# sensorboardschematic.net
KiCad netlist of a schematic drawn in EasyEDA Pro
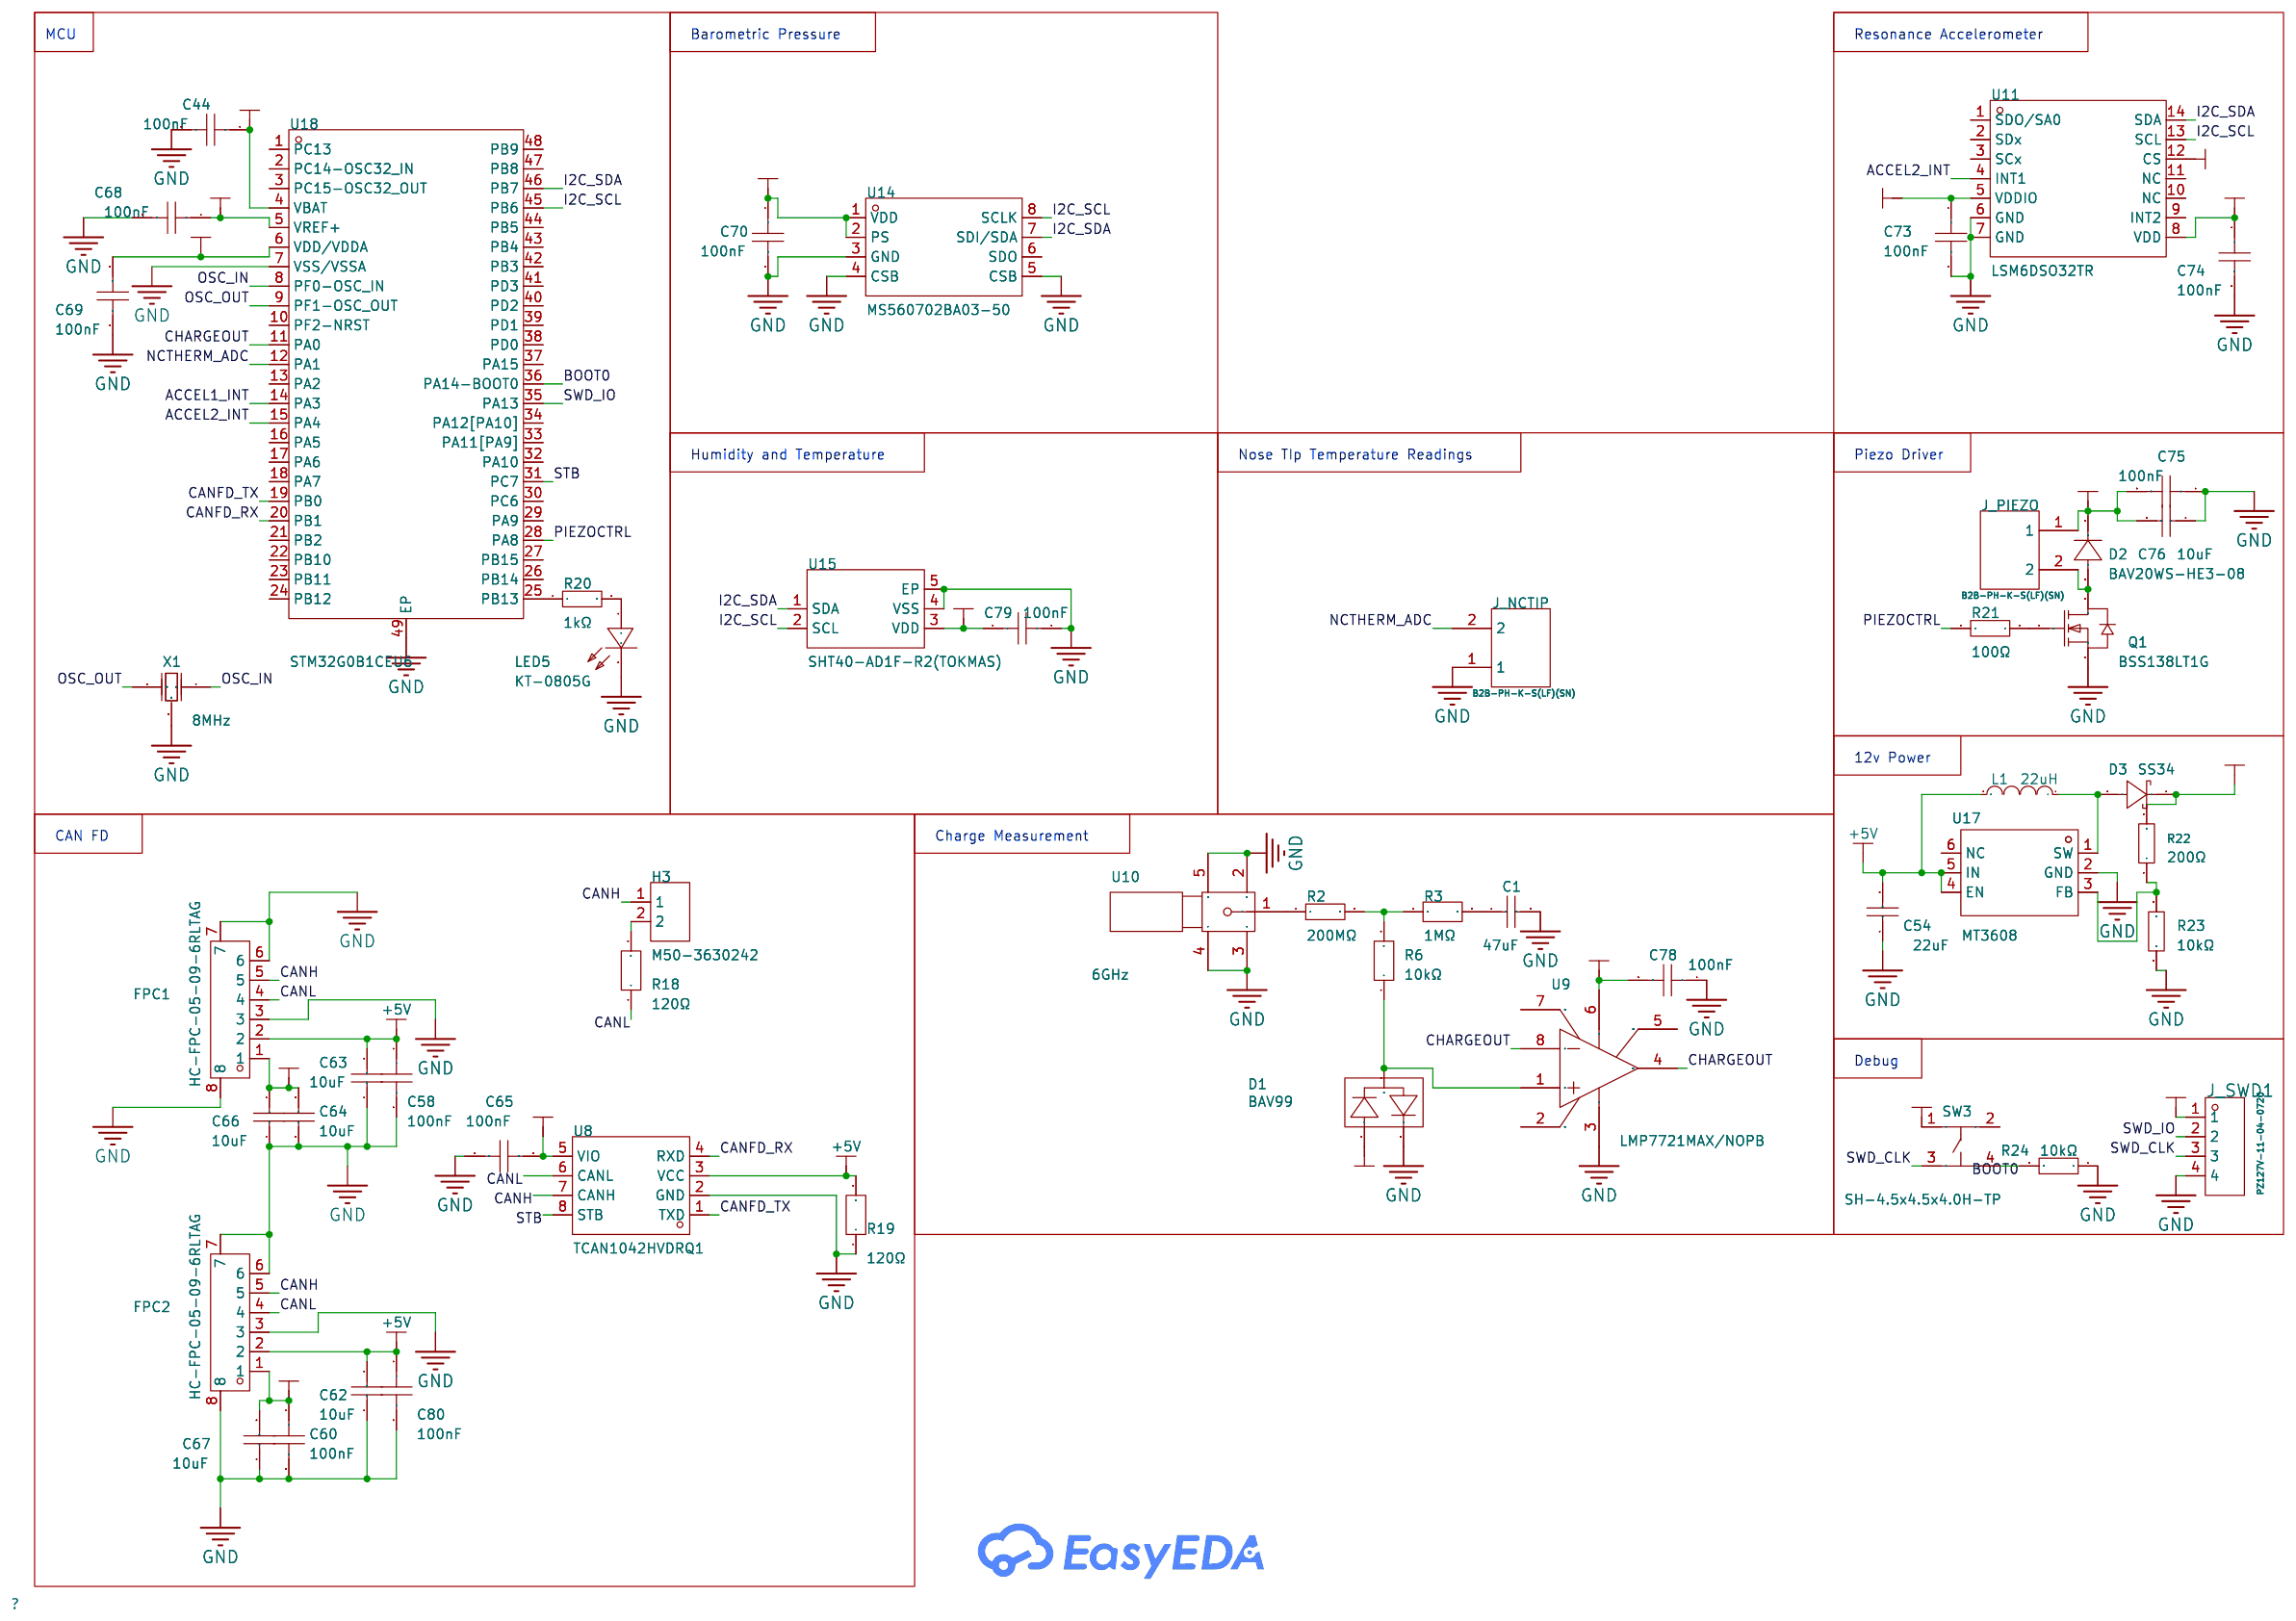
[diagram p0: schematic sheet]

(export (version "E")
  (design (tool "Eeschema 10.0.6"))
  (components
    (comp (ref "C1")
      (value "47uF")
      (footprint "easyedapro:C0805")
      (description "Capacitance:47uF Tolerance:±20% Tolerance:±20% Voltage Rating:6.3V Temperature Coefficient:X5R")
      (fields
        (field (name "Manufacturer Part") "CL21A476MQYNNNE")
        (field (name "Manufacturer") "SAMSUNG(三星)")
      )
      (libsource (lib "easyedapro") (part "CL21A476MQYNNNE"))
    )
    (comp (ref "C44")
      (value "100nF")
      (footprint "easyedapro:C0402")
      (description "Capacitance:100nF Tolerance:±10% Tolerance:±10% Voltage Rating:16V Temperature Coefficient:X7R")
      (fields
        (field (name "Manufacturer Part") "CL05B104KO5NNNC")
        (field (name "Manufacturer") "SAMSUNG(三星)")
      )
      (libsource (lib "easyedapro") (part "CL05B104KO5NNNC"))
    )
    (comp (ref "C54")
      (value "22uF")
      (footprint "easyedapro:C1206")
      (description "Capacitance:22uF Tolerance:±10% Tolerance:±10% Voltage Rating:25V Temperature Coefficient:X5R")
      (fields
        (field (name "Manufacturer Part") "CL31A226KAHNNNE")
        (field (name "Manufacturer") "SAMSUNG(三星)")
      )
      (libsource (lib "easyedapro") (part "CL31A226KAHNNNE"))
    )
    (comp (ref "C58")
      (value "100nF")
      (footprint "easyedapro:C0402")
      (description "Capacitance:100nF Tolerance:±10% Tolerance:±10% Voltage Rating:16V Temperature Coefficient:X7R")
      (fields
        (field (name "Manufacturer Part") "CL05B104KO5NNNC")
        (field (name "Manufacturer") "SAMSUNG(三星)")
      )
      (libsource (lib "easyedapro") (part "CL05B104KO5NNNC"))
    )
    (comp (ref "C60")
      (value "100nF")
      (footprint "easyedapro:C0402")
      (description "Capacitance:100nF Tolerance:±10% Tolerance:±10% Voltage Rating:16V Temperature Coefficient:X7R")
      (fields
        (field (name "Manufacturer Part") "CL05B104KO5NNNC")
        (field (name "Manufacturer") "SAMSUNG(三星)")
      )
      (libsource (lib "easyedapro") (part "CL05B104KO5NNNC"))
    )
    (comp (ref "C62")
      (value "10uF")
      (footprint "easyedapro:C0402")
      (description "Capacitance:10uF Tolerance:±20% Tolerance:±20% Voltage Rating:6.3V Temperature Coefficient:X5R")
      (fields
        (field (name "Manufacturer Part") "CL05A106MQ5NUNC")
        (field (name "Manufacturer") "SAMSUNG(三星)")
      )
      (libsource (lib "easyedapro") (part "CL05A106MQ5NUNC"))
    )
    (comp (ref "C63")
      (value "10uF")
      (footprint "easyedapro:C0402")
      (description "Capacitance:10uF Tolerance:±20% Tolerance:±20% Voltage Rating:6.3V Temperature Coefficient:X5R")
      (fields
        (field (name "Manufacturer Part") "CL05A106MQ5NUNC")
        (field (name "Manufacturer") "SAMSUNG(三星)")
      )
      (libsource (lib "easyedapro") (part "CL05A106MQ5NUNC"))
    )
    (comp (ref "C64")
      (value "10uF")
      (footprint "easyedapro:C0402")
      (description "Capacitance:10uF Tolerance:±20% Tolerance:±20% Voltage Rating:6.3V Temperature Coefficient:X5R")
      (fields
        (field (name "Manufacturer Part") "CL05A106MQ5NUNC")
        (field (name "Manufacturer") "SAMSUNG(三星)")
      )
      (libsource (lib "easyedapro") (part "CL05A106MQ5NUNC"))
    )
    (comp (ref "C65")
      (value "100nF")
      (footprint "easyedapro:C0402")
      (description "Capacitance:100nF Tolerance:±10% Tolerance:±10% Voltage Rating:16V Temperature Coefficient:X7R")
      (fields
        (field (name "Manufacturer Part") "CL05B104KO5NNNC")
        (field (name "Manufacturer") "SAMSUNG(三星)")
      )
      (libsource (lib "easyedapro") (part "CL05B104KO5NNNC"))
    )
    (comp (ref "C66")
      (value "10uF")
      (footprint "easyedapro:C0402")
      (description "Capacitance:10uF Tolerance:±20% Tolerance:±20% Voltage Rating:6.3V Temperature Coefficient:X5R")
      (fields
        (field (name "Manufacturer Part") "CL05A106MQ5NUNC")
        (field (name "Manufacturer") "SAMSUNG(三星)")
      )
      (libsource (lib "easyedapro") (part "CL05A106MQ5NUNC"))
    )
    (comp (ref "C67")
      (value "10uF")
      (footprint "easyedapro:C0402")
      (description "Capacitance:10uF Tolerance:±20% Tolerance:±20% Voltage Rating:6.3V Temperature Coefficient:X5R")
      (fields
        (field (name "Manufacturer Part") "CL05A106MQ5NUNC")
        (field (name "Manufacturer") "SAMSUNG(三星)")
      )
      (libsource (lib "easyedapro") (part "CL05A106MQ5NUNC"))
    )
    (comp (ref "C68")
      (value "100nF")
      (footprint "easyedapro:C0402")
      (description "Capacitance:100nF Tolerance:±10% Tolerance:±10% Voltage Rating:16V Temperature Coefficient:X7R")
      (fields
        (field (name "Manufacturer Part") "CL05B104KO5NNNC")
        (field (name "Manufacturer") "SAMSUNG(三星)")
      )
      (libsource (lib "easyedapro") (part "CL05B104KO5NNNC"))
    )
    (comp (ref "C69")
      (value "100nF")
      (footprint "easyedapro:C0402")
      (description "Capacitance:100nF Tolerance:±10% Tolerance:±10% Voltage Rating:16V Temperature Coefficient:X7R")
      (fields
        (field (name "Manufacturer Part") "CL05B104KO5NNNC")
        (field (name "Manufacturer") "SAMSUNG(三星)")
      )
      (libsource (lib "easyedapro") (part "CL05B104KO5NNNC"))
    )
    (comp (ref "C70")
      (value "100nF")
      (footprint "easyedapro:C0402")
      (description "Capacitance:100nF Tolerance:±10% Tolerance:±10% Voltage Rating:16V Temperature Coefficient:X7R")
      (fields
        (field (name "Manufacturer Part") "CL05B104KO5NNNC")
        (field (name "Manufacturer") "SAMSUNG(三星)")
      )
      (libsource (lib "easyedapro") (part "CL05B104KO5NNNC"))
    )
    (comp (ref "C73")
      (value "100nF")
      (footprint "easyedapro:C0402")
      (description "Capacitance:100nF Tolerance:±10% Tolerance:±10% Voltage Rating:16V Temperature Coefficient:X7R")
      (fields
        (field (name "Manufacturer Part") "CL05B104KO5NNNC")
        (field (name "Manufacturer") "SAMSUNG(三星)")
      )
      (libsource (lib "easyedapro") (part "CL05B104KO5NNNC"))
    )
    (comp (ref "C74")
      (value "100nF")
      (footprint "easyedapro:C0402")
      (description "Capacitance:100nF Tolerance:±10% Tolerance:±10% Voltage Rating:16V Temperature Coefficient:X7R")
      (fields
        (field (name "Manufacturer Part") "CL05B104KO5NNNC")
        (field (name "Manufacturer") "SAMSUNG(三星)")
      )
      (libsource (lib "easyedapro") (part "CL05B104KO5NNNC"))
    )
    (comp (ref "C75")
      (value "100nF")
      (footprint "easyedapro:C0402")
      (description "Capacitance:100nF Tolerance:±10% Tolerance:±10% Voltage Rating:16V Temperature Coefficient:X7R")
      (fields
        (field (name "Manufacturer Part") "CL05B104KO5NNNC")
        (field (name "Manufacturer") "SAMSUNG(三星)")
      )
      (libsource (lib "easyedapro") (part "CL05B104KO5NNNC"))
    )
    (comp (ref "C76")
      (value "10uF")
      (footprint "easyedapro:C0402")
      (description "Capacitance:10uF Tolerance:±20% Tolerance:±20% Voltage Rating:6.3V Temperature Coefficient:X5R")
      (fields
        (field (name "Manufacturer Part") "CL05A106MQ5NUNC")
        (field (name "Manufacturer") "SAMSUNG(三星)")
      )
      (libsource (lib "easyedapro") (part "CL05A106MQ5NUNC"))
    )
    (comp (ref "C78")
      (value "100nF")
      (footprint "easyedapro:C0402")
      (description "Capacitance:100nF Tolerance:±10% Tolerance:±10% Voltage Rating:16V Temperature Coefficient:X7R")
      (fields
        (field (name "Manufacturer Part") "CL05B104KO5NNNC")
        (field (name "Manufacturer") "SAMSUNG(三星)")
      )
      (libsource (lib "easyedapro") (part "CL05B104KO5NNNC"))
    )
    (comp (ref "C79")
      (value "100nF")
      (footprint "easyedapro:C0402")
      (description "Capacitance:100nF Tolerance:±10% Tolerance:±10% Voltage Rating:16V Temperature Coefficient:X7R")
      (fields
        (field (name "Manufacturer Part") "CL05B104KO5NNNC")
        (field (name "Manufacturer") "SAMSUNG(三星)")
      )
      (libsource (lib "easyedapro") (part "CL05B104KO5NNNC"))
    )
    (comp (ref "C80")
      (value "100nF")
      (footprint "easyedapro:C0402")
      (description "Capacitance:100nF Tolerance:±10% Tolerance:±10% Voltage Rating:16V Temperature Coefficient:X7R")
      (fields
        (field (name "Manufacturer Part") "CL05B104KO5NNNC")
        (field (name "Manufacturer") "SAMSUNG(三星)")
      )
      (libsource (lib "easyedapro") (part "CL05B104KO5NNNC"))
    )
    (comp (ref "D1")
      (value "BAV99")
      (footprint "easyedapro:SOT-23-3_L2.9-W1.3-P1.90-LS2.4-BR")
      (fields (field (name "Manufacturer") "JSMSEMI(杰盛微)"))
      (libsource (lib "easyedapro") (part "BAV99_C916421"))
    )
    (comp (ref "D2")
      (value "BAV20WS-HE3-08")
      (footprint "easyedapro:SOD-323_L1.8-W1.3-LS2.7-RD")
      (fields (field (name "Manufacturer") "VISHAY(威世)"))
      (libsource (lib "easyedapro") (part "BAV20WS-HE3-08"))
    )
    (comp (ref "D3")
      (value "SS34")
      (footprint "easyedapro:SMA_L4.2-W2.7-LS5.0-RD")
      (fields (field (name "Manufacturer") "JSMSEMI(杰盛微)"))
      (libsource (lib "easyedapro") (part "SS34_C2837271"))
    )
    (comp (ref "FPC1")
      (value "HC-FPC-05-09-6RLTAG")
      (footprint "easyedapro:FPC-SMD_6P-P0.50_HC-FPC-05-09-6RLTAG")
      (fields (field (name "Manufacturer") "HCTL(华灿天禄)"))
      (libsource (lib "easyedapro") (part "HC-FPC-05-09-6RLTAG"))
    )
    (comp (ref "FPC2")
      (value "HC-FPC-05-09-6RLTAG")
      (footprint "easyedapro:FPC-SMD_6P-P0.50_HC-FPC-05-09-6RLTAG")
      (fields (field (name "Manufacturer") "HCTL(华灿天禄)"))
      (libsource (lib "easyedapro") (part "HC-FPC-05-09-6RLTAG"))
    )
    (comp (ref "H3")
      (value "M50-3630242")
      (footprint "easyedapro:HDR-SMD_2P-P1.27_M50-3630242")
      (fields (field (name "Manufacturer") "Harwin"))
      (libsource (lib "easyedapro") (part "M50-3630242"))
    )
    (comp (ref "J_NCTIP")
      (value "B2B-PH-K-S(LF)(SN)")
      (footprint "easyedapro:CONN-TH_B2B-PH-K-S")
      (fields (field (name "Manufacturer") "JST"))
      (libsource (lib "easyedapro") (part "B2B-PH-K-S(LF)(SN)"))
    )
    (comp (ref "J_PIEZO")
      (value "B2B-PH-K-S(LF)(SN)")
      (footprint "easyedapro:CONN-TH_B2B-PH-K-S")
      (fields (field (name "Manufacturer") "JST"))
      (libsource (lib "easyedapro") (part "B2B-PH-K-S(LF)(SN)"))
    )
    (comp (ref "J_SWD1")
      (value "PZ127V-11-04-0720")
      (footprint "easyedapro:HDR-TH_4P-P1.27-V-M")
      (fields (field (name "Manufacturer") "XFCN(兴飞)"))
      (libsource (lib "easyedapro") (part "PZ127V-11-04-0720"))
    )
    (comp (ref "L1")
      (value "22uH")
      (footprint "easyedapro:IND-SMD_L3.2-W2.5")
      (fields (field (name "Manufacturer Part") "NLV32T-220J-EF") (field (name "Manufacturer") "TDK"))
      (libsource (lib "easyedapro") (part "NLV32T-220J-EF"))
    )
    (comp (ref "LED5")
      (value "KT-0805G")
      (footprint "easyedapro:LED0805-R-RD")
      (fields (field (name "Manufacturer") "KENTO"))
      (libsource (lib "easyedapro") (part "0805G (Green)"))
    )
    (comp (ref "Q1")
      (value "BSS138LT1G")
      (footprint "easyedapro:SOT-23-3_L2.9-W1.6-P1.90-LS2.8-BR")
      (fields (field (name "Manufacturer") "onsemi(安森美)"))
      (libsource (lib "easyedapro") (part "BSS138LT1G"))
    )
    (comp (ref "R2")
      (value "200MΩ")
      (footprint "easyedapro:RES-TH_L14.7-W2.54-P10.2-D0.8")
      (fields (field (name "Manufacturer Part") "SM102032006FE") (field (name "Manufacturer") "Ohmite"))
      (libsource (lib "easyedapro") (part "SM102032006FE"))
    )
    (comp (ref "R3")
      (value "1MΩ")
      (footprint "easyedapro:R0402")
      (fields (field (name "Manufacturer Part") "FRC0402F1004TS") (field (name "Manufacturer") "FOJAN(富捷)"))
      (libsource (lib "easyedapro") (part "FRC0402F1004TS"))
    )
    (comp (ref "R6")
      (value "10kΩ")
      (footprint "easyedapro:R0402")
      (fields (field (name "Manufacturer Part") "FRC0402F1002TS") (field (name "Manufacturer") "FOJAN(富捷)"))
      (libsource (lib "easyedapro") (part "FRC0402F1002TS"))
    )
    (comp (ref "R18")
      (value "120Ω")
      (footprint "easyedapro:R0402")
      (fields (field (name "Manufacturer Part") "FRC0402F1200TS") (field (name "Manufacturer") "FOJAN(富捷)"))
      (libsource (lib "easyedapro") (part "FRC0402F1200TS"))
    )
    (comp (ref "R19")
      (value "120Ω")
      (footprint "easyedapro:R0402")
      (fields (field (name "Manufacturer Part") "FRC0402F1200TS") (field (name "Manufacturer") "FOJAN(富捷)"))
      (libsource (lib "easyedapro") (part "FRC0402F1200TS"))
    )
    (comp (ref "R20")
      (value "1kΩ")
      (footprint "easyedapro:R0402")
      (fields
        (field (name "Manufacturer Part") "0402WGF1001TCE")
        (field (name "Manufacturer") "UNI-ROYAL(厚声)")
      )
      (libsource (lib "easyedapro") (part "0402WGF1001TCE"))
    )
    (comp (ref "R21")
      (value "100Ω")
      (footprint "easyedapro:R0402")
      (fields
        (field (name "Manufacturer Part") "0402WGF1000TCE")
        (field (name "Manufacturer") "UNI-ROYAL(厚声)")
      )
      (libsource (lib "easyedapro") (part "0402WGF1000TCE"))
    )
    (comp (ref "R22")
      (value "200Ω")
      (footprint "easyedapro:R0603")
      (fields
        (field (name "Manufacturer Part") "0603WAF2000T5E")
        (field (name "Manufacturer") "UNI-ROYAL(厚声)")
      )
      (libsource (lib "easyedapro") (part "0603WAF2000T5E"))
    )
    (comp (ref "R23")
      (value "10kΩ")
      (footprint "easyedapro:R0402")
      (fields
        (field (name "Manufacturer Part") "0402WGF1002TCE")
        (field (name "Manufacturer") "UNI-ROYAL(厚声)")
      )
      (libsource (lib "easyedapro") (part "0402WGF1002TCE"))
    )
    (comp (ref "R24")
      (value "10kΩ")
      (footprint "easyedapro:R0402")
      (fields
        (field (name "Manufacturer Part") "0402WGF1002TCE")
        (field (name "Manufacturer") "UNI-ROYAL(厚声)")
      )
      (libsource (lib "easyedapro") (part "0402WGF1002TCE"))
    )
    (comp (ref "SW3")
      (value "SH-4.5x4.5x4.0H-TP")
      (footprint "easyedapro:SW-SMD_4P-SH-4.5X4.5X4.0H-TP")
      (fields (field (name "Manufacturer") "SHOU HAN(首韩)"))
      (libsource (lib "easyedapro") (part "SH-4.5X4.5X4.0H-TP"))
    )
    (comp (ref "U8")
      (value "TCAN1042HVDRQ1")
      (footprint "easyedapro:SOIC-8_L4.9-W3.9-P1.27-LS6.0-BL")
      (fields (field (name "Manufacturer") "TI(德州仪器)"))
      (libsource (lib "easyedapro") (part "TCAN1042HVDRQ1"))
    )
    (comp (ref "U9")
      (value "LMP7721MAX/NOPB")
      (footprint "easyedapro:SOIC-8_L4.9-W3.9-P1.27-LS6.0-BL")
      (fields (field (name "Manufacturer") "TI(德州仪器)"))
      (libsource (lib "easyedapro") (part "LMP7721MAX/NOPB"))
    )
    (comp (ref "U10")
      (value "6GHz")
      (footprint "easyedapro:MMCX-TH_DL-MMCX-KWE")
      (fields
        (field (name "Manufacturer Part") "BWMMCX-KWE")
        (field (name "Manufacturer") "BAT WIRELESS(蝙蝠无线)")
      )
      (libsource (lib "easyedapro") (part "BWMMCX-KWE"))
    )
    (comp (ref "U11")
      (value "LSM6DSO32TR")
      (footprint "easyedapro:LGA-14_L3.0-W2.5-P0.50-TL")
      (description "Sensor Type:加速度计陀螺仪 Operating Temperature:-40°C~+85°C Operating Temperature:-40°C~+85°C")
      (fields (field (name "Manufacturer") "ST(意法半导体)"))
      (libsource (lib "easyedapro") (part "LSM6DSO32TR"))
    )
    (comp (ref "U14")
      (value "MS560702BA03-50")
      (footprint "easyedapro:SENSOR-SMD_MS560702BA03-50")
      (fields (field (name "Manufacturer") "TE Connectivity(泰科电子)"))
      (libsource (lib "easyedapro") (part "MS560702BA03-50"))
    )
    (comp (ref "U15")
      (value "SHT40-AD1F-R2(TOKMAS)")
      (footprint "easyedapro:DFN-4_L1.5-W1.5-P0.80-TL-EP")
      (fields (field (name "Manufacturer") "Tokmas(托克马斯)"))
      (libsource (lib "easyedapro") (part "SHT40-AD1F-R2(TOKMAS)"))
    )
    (comp (ref "U17")
      (value "MT3608")
      (footprint "easyedapro:SOT-23-6_L2.9-W1.6-P0.95-LS2.8-BL")
      (fields (field (name "Manufacturer") "西安航天民芯"))
      (libsource (lib "easyedapro") (part "MT3608"))
    )
    (comp (ref "U18")
      (value "STM32G0B1CEU6")
      (footprint "easyedapro:UFQFPN-48_L7.0-W7.0-P0.50-BL-EP")
      (fields (field (name "Manufacturer") "ST(意法半导体)"))
      (libsource (lib "easyedapro") (part "STM32G0B1CEU6"))
    )
    (comp (ref "X1")
      (value "8MHz")
      (footprint "easyedapro:OSC-SMD_3P-L3.2-W1.3-P1.20-L")
      (fields
        (field (name "Manufacturer Part") "CSTNE8M00GH5C000R0")
        (field (name "Manufacturer") "muRata(村田)")
      )
      (libsource (lib "easyedapro") (part "CSTNE8M00GH5C000R0"))
    )
  )
  (nets
    (net (code "1") (name "+5V") (class "Default")
      (node (ref "C54") (pin "2") (pinfunction "2_2") (pintype "input"))
      (node (ref "C58") (pin "1") (pinfunction "1_1") (pintype "unspecified"))
      (node (ref "C62") (pin "2") (pinfunction "2_2") (pintype "input"))
      (node (ref "C63") (pin "2") (pinfunction "2_2") (pintype "input"))
      (node (ref "C80") (pin "1") (pinfunction "1_1") (pintype "unspecified"))
      (node (ref "FPC1") (pin "2") (pinfunction "2_2") (pintype "unspecified"))
      (node (ref "FPC2") (pin "2") (pinfunction "2_2") (pintype "unspecified"))
      (node (ref "L1") (pin "2") (pinfunction "2_2") (pintype "unspecified"))
      (node (ref "R19") (pin "2") (pinfunction "2_2") (pintype "unspecified"))
      (node (ref "U17") (pin "4") (pinfunction "EN_4") (pintype "unspecified"))
      (node (ref "U17") (pin "5") (pinfunction "IN_5") (pintype "unspecified"))
      (node (ref "U8") (pin "3") (pinfunction "VCC_3") (pintype "unspecified"))
    )
    (net (code "2") (name "+12V") (class "Default")
      (node (ref "C75") (pin "2") (pinfunction "2_2") (pintype "unspecified"))
      (node (ref "C76") (pin "2") (pinfunction "2_2") (pintype "input"))
      (node (ref "D2") (pin "1") (pinfunction "C_1") (pintype "unspecified"))
      (node (ref "D3") (pin "1") (pinfunction "K_1") (pintype "unspecified"))
      (node (ref "J_PIEZO") (pin "1") (pinfunction "1_1") (pintype "input"))
      (node (ref "R22") (pin "2") (pinfunction "2_2") (pintype "input"))
    )
    (net (code "3") (name "/ACCEL1_INT") (class "Default")
      (node (ref "U18") (pin "14") (pinfunction "PA3_14") (pintype "unspecified"))
    )
    (net (code "4") (name "/ACCEL2_INT") (class "Default")
      (node (ref "U11") (pin "4") (pinfunction "INT1_4") (pintype "input"))
      (node (ref "U18") (pin "15") (pinfunction "PA4_15") (pintype "unspecified"))
    )
    (net (code "5") (name "/BOOT0") (class "Default")
      (node (ref "R24") (pin "2") (pinfunction "2_2") (pintype "input"))
      (node (ref "SW3") (pin "4") (pinfunction "4_4") (pintype "unspecified"))
      (node (ref "U18") (pin "36") (pinfunction "PA14-BOOT0_36") (pintype "unspecified"))
    )
    (net (code "6") (name "/CANFD_RX") (class "Default")
      (node (ref "U18") (pin "20") (pinfunction "PB1_20") (pintype "unspecified"))
      (node (ref "U8") (pin "4") (pinfunction "RXD_4") (pintype "unspecified"))
    )
    (net (code "7") (name "/CANFD_TX") (class "Default")
      (node (ref "U18") (pin "19") (pinfunction "PB0_19") (pintype "unspecified"))
      (node (ref "U8") (pin "1") (pinfunction "TXD_1") (pintype "unspecified"))
    )
    (net (code "8") (name "/CANH") (class "Default")
      (node (ref "FPC1") (pin "5") (pinfunction "5_5") (pintype "unspecified"))
      (node (ref "FPC2") (pin "5") (pinfunction "5_5") (pintype "unspecified"))
      (node (ref "H3") (pin "1") (pinfunction "1_1") (pintype "unspecified"))
      (node (ref "U8") (pin "7") (pinfunction "CANH_7") (pintype "unspecified"))
    )
    (net (code "9") (name "/CANL") (class "Default")
      (node (ref "FPC1") (pin "4") (pinfunction "4_4") (pintype "unspecified"))
      (node (ref "FPC2") (pin "4") (pinfunction "4_4") (pintype "unspecified"))
      (node (ref "R18") (pin "1") (pinfunction "1_1") (pintype "unspecified"))
      (node (ref "U8") (pin "6") (pinfunction "CANL_6") (pintype "unspecified"))
    )
    (net (code "10") (name "/CHARGEOUT") (class "Default")
      (node (ref "U18") (pin "11") (pinfunction "PA0_11") (pintype "unspecified"))
      (node (ref "U9") (pin "4") (pinfunction "VOUT_4") (pintype "output"))
      (node (ref "U9") (pin "8") (pinfunction "-IN_8") (pintype "unspecified"))
    )
    (net (code "11") (name "/I2C_SCL") (class "Default")
      (node (ref "U11") (pin "13") (pinfunction "SCL_13") (pintype "input"))
      (node (ref "U14") (pin "8") (pinfunction "SCLK_8") (pintype "unspecified"))
      (node (ref "U15") (pin "2") (pinfunction "SCL_2") (pintype "unspecified"))
      (node (ref "U18") (pin "45") (pinfunction "PB6_45") (pintype "unspecified"))
    )
    (net (code "12") (name "/I2C_SDA") (class "Default")
      (node (ref "U11") (pin "14") (pinfunction "SDA_14") (pintype "input"))
      (node (ref "U14") (pin "7") (pinfunction "SDI/SDA_7") (pintype "unspecified"))
      (node (ref "U15") (pin "1") (pinfunction "SDA_1") (pintype "unspecified"))
      (node (ref "U18") (pin "46") (pinfunction "PB7_46") (pintype "unspecified"))
    )
    (net (code "13") (name "/NCTHERM_ADC") (class "Default")
      (node (ref "J_NCTIP") (pin "2") (pinfunction "2_2") (pintype "input"))
      (node (ref "U18") (pin "12") (pinfunction "PA1_12") (pintype "unspecified"))
    )
    (net (code "14") (name "/OSC_IN") (class "Default")
      (node (ref "U18") (pin "8") (pinfunction "PF0-OSC_IN_8") (pintype "unspecified"))
      (node (ref "X1") (pin "1") (pinfunction "OSC1_1") (pintype "input"))
    )
    (net (code "15") (name "/OSC_OUT") (class "Default")
      (node (ref "U18") (pin "9") (pinfunction "PF1-OSC_OUT_9") (pintype "unspecified"))
      (node (ref "X1") (pin "3") (pinfunction "OSC2_3") (pintype "input"))
    )
    (net (code "16") (name "/PIEZOCTRL") (class "Default")
      (node (ref "R21") (pin "1") (pinfunction "1_1") (pintype "input"))
      (node (ref "U18") (pin "28") (pinfunction "PA8_28") (pintype "unspecified"))
    )
    (net (code "17") (name "/STB") (class "Default")
      (node (ref "U18") (pin "31") (pinfunction "PC7_31") (pintype "unspecified"))
      (node (ref "U8") (pin "8") (pinfunction "STB_8") (pintype "unspecified"))
    )
    (net (code "18") (name "/SWD_CLK") (class "Default")
      (node (ref "J_SWD1") (pin "3") (pinfunction "3_3") (pintype "input"))
      (node (ref "SW3") (pin "3") (pinfunction "3_3") (pintype "unspecified"))
    )
    (net (code "19") (name "/SWD_IO") (class "Default")
      (node (ref "J_SWD1") (pin "2") (pinfunction "2_2") (pintype "input"))
      (node (ref "U18") (pin "35") (pinfunction "PA13_35") (pintype "unspecified"))
    )
    (net (code "20") (name "3V3") (class "Default")
      (node (ref "C44") (pin "1") (pinfunction "1_1") (pintype "unspecified"))
      (node (ref "C60") (pin "1") (pinfunction "1_1") (pintype "unspecified"))
      (node (ref "C64") (pin "2") (pinfunction "2_2") (pintype "input"))
      (node (ref "C65") (pin "2") (pinfunction "2_2") (pintype "unspecified"))
      (node (ref "C66") (pin "2") (pinfunction "2_2") (pintype "input"))
      (node (ref "C67") (pin "2") (pinfunction "2_2") (pintype "input"))
      (node (ref "C68") (pin "1") (pinfunction "1_1") (pintype "unspecified"))
      (node (ref "C69") (pin "2") (pinfunction "2_2") (pintype "unspecified"))
      (node (ref "C70") (pin "1") (pinfunction "1_1") (pintype "unspecified"))
      (node (ref "C73") (pin "1") (pinfunction "1_1") (pintype "unspecified"))
      (node (ref "C74") (pin "1") (pinfunction "1_1") (pintype "unspecified"))
      (node (ref "C78") (pin "2") (pinfunction "2_2") (pintype "unspecified"))
      (node (ref "C79") (pin "2") (pinfunction "2_2") (pintype "unspecified"))
      (node (ref "D1") (pin "1") (pinfunction "1_1") (pintype "unspecified"))
      (node (ref "FPC1") (pin "1") (pinfunction "1_1") (pintype "unspecified"))
      (node (ref "FPC2") (pin "1") (pinfunction "1_1") (pintype "unspecified"))
      (node (ref "J_SWD1") (pin "1") (pinfunction "1_1") (pintype "input"))
      (node (ref "SW3") (pin "1") (pinfunction "1_1") (pintype "unspecified"))
      (node (ref "U11") (pin "12") (pinfunction "CS_12") (pintype "input"))
      (node (ref "U11") (pin "5") (pinfunction "VDDIO_5") (pintype "input"))
      (node (ref "U11") (pin "8") (pinfunction "VDD_8") (pintype "input"))
      (node (ref "U14") (pin "1") (pinfunction "VDD_1") (pintype "unspecified"))
      (node (ref "U14") (pin "2") (pinfunction "PS_2") (pintype "unspecified"))
      (node (ref "U15") (pin "3") (pinfunction "VDD_3") (pintype "unspecified"))
      (node (ref "U18") (pin "4") (pinfunction "VBAT_4") (pintype "unspecified"))
      (node (ref "U18") (pin "5") (pinfunction "VREF+_5") (pintype "unspecified"))
      (node (ref "U18") (pin "6") (pinfunction "VDD/VDDA_6") (pintype "unspecified"))
      (node (ref "U8") (pin "5") (pinfunction "VIO_5") (pintype "unspecified"))
      (node (ref "U9") (pin "6") (pinfunction "V+_6") (pintype "unspecified"))
    )
    (net (code "21") (name "GND") (class "Default")
      (node (ref "C1") (pin "2") (pinfunction "2_2") (pintype "input"))
      (node (ref "C44") (pin "2") (pinfunction "2_2") (pintype "unspecified"))
      (node (ref "C54") (pin "1") (pinfunction "1_1") (pintype "input"))
      (node (ref "C58") (pin "2") (pinfunction "2_2") (pintype "unspecified"))
      (node (ref "C60") (pin "2") (pinfunction "2_2") (pintype "unspecified"))
      (node (ref "C62") (pin "1") (pinfunction "1_1") (pintype "input"))
      (node (ref "C63") (pin "1") (pinfunction "1_1") (pintype "input"))
      (node (ref "C64") (pin "1") (pinfunction "1_1") (pintype "input"))
      (node (ref "C65") (pin "1") (pinfunction "1_1") (pintype "unspecified"))
      (node (ref "C66") (pin "1") (pinfunction "1_1") (pintype "input"))
      (node (ref "C67") (pin "1") (pinfunction "1_1") (pintype "input"))
      (node (ref "C68") (pin "2") (pinfunction "2_2") (pintype "unspecified"))
      (node (ref "C69") (pin "1") (pinfunction "1_1") (pintype "unspecified"))
      (node (ref "C70") (pin "2") (pinfunction "2_2") (pintype "unspecified"))
      (node (ref "C73") (pin "2") (pinfunction "2_2") (pintype "unspecified"))
      (node (ref "C74") (pin "2") (pinfunction "2_2") (pintype "unspecified"))
      (node (ref "C75") (pin "1") (pinfunction "1_1") (pintype "unspecified"))
      (node (ref "C76") (pin "1") (pinfunction "1_1") (pintype "input"))
      (node (ref "C78") (pin "1") (pinfunction "1_1") (pintype "unspecified"))
      (node (ref "C79") (pin "1") (pinfunction "1_1") (pintype "unspecified"))
      (node (ref "C80") (pin "2") (pinfunction "2_2") (pintype "unspecified"))
      (node (ref "D1") (pin "2") (pinfunction "2_2") (pintype "unspecified"))
      (node (ref "FPC1") (pin "3") (pinfunction "3_3") (pintype "unspecified"))
      (node (ref "FPC1") (pin "6") (pinfunction "6_6") (pintype "unspecified"))
      (node (ref "FPC1") (pin "7") (pinfunction "7_7") (pintype "unspecified"))
      (node (ref "FPC1") (pin "8") (pinfunction "8_8") (pintype "unspecified"))
      (node (ref "FPC2") (pin "3") (pinfunction "3_3") (pintype "unspecified"))
      (node (ref "FPC2") (pin "6") (pinfunction "6_6") (pintype "unspecified"))
      (node (ref "FPC2") (pin "7") (pinfunction "7_7") (pintype "unspecified"))
      (node (ref "FPC2") (pin "8") (pinfunction "8_8") (pintype "unspecified"))
      (node (ref "J_NCTIP") (pin "1") (pinfunction "1_1") (pintype "input"))
      (node (ref "J_SWD1") (pin "4") (pinfunction "4_4") (pintype "input"))
      (node (ref "LED5") (pin "2") (pinfunction "K_2") (pintype "unspecified"))
      (node (ref "Q1") (pin "2") (pinfunction "S_2") (pintype "unspecified"))
      (node (ref "R19") (pin "1") (pinfunction "1_1") (pintype "unspecified"))
      (node (ref "R23") (pin "1") (pinfunction "1_1") (pintype "input"))
      (node (ref "R24") (pin "1") (pinfunction "1_1") (pintype "input"))
      (node (ref "U10") (pin "2") (pinfunction "2_2") (pintype "unspecified"))
      (node (ref "U10") (pin "3") (pinfunction "3_3") (pintype "unspecified"))
      (node (ref "U10") (pin "4") (pinfunction "4_4") (pintype "unspecified"))
      (node (ref "U10") (pin "5") (pinfunction "5_5") (pintype "unspecified"))
      (node (ref "U11") (pin "6") (pinfunction "GND_6") (pintype "input"))
      (node (ref "U11") (pin "7") (pinfunction "GND_7") (pintype "input"))
      (node (ref "U14") (pin "3") (pinfunction "GND_3") (pintype "unspecified"))
      (node (ref "U14") (pin "4") (pinfunction "CSB_4") (pintype "unspecified"))
      (node (ref "U14") (pin "5") (pinfunction "CSB_5") (pintype "unspecified"))
      (node (ref "U15") (pin "4") (pinfunction "VSS_4") (pintype "unspecified"))
      (node (ref "U15") (pin "5") (pinfunction "EP_5") (pintype "unspecified"))
      (node (ref "U17") (pin "2") (pinfunction "GND_2") (pintype "unspecified"))
      (node (ref "U18") (pin "49") (pinfunction "EP_49") (pintype "unspecified"))
      (node (ref "U18") (pin "7") (pinfunction "VSS/VSSA_7") (pintype "unspecified"))
      (node (ref "U8") (pin "2") (pinfunction "GND_2") (pintype "unspecified"))
      (node (ref "U9") (pin "3") (pinfunction "V-_3") (pintype "unspecified"))
      (node (ref "X1") (pin "2") (pinfunction "GND_2") (pintype "input"))
    )
    (net (code "22") (name "Net-(C1-Pad1)") (class "Default")
      (node (ref "C1") (pin "1") (pinfunction "1_1") (pintype "input"))
      (node (ref "R3") (pin "2") (pinfunction "2_2") (pintype "unspecified"))
    )
    (net (code "23") (name "Net-(D2-A)") (class "Default")
      (node (ref "D2") (pin "2") (pinfunction "A_2") (pintype "unspecified"))
      (node (ref "J_PIEZO") (pin "2") (pinfunction "2_2") (pintype "input"))
      (node (ref "Q1") (pin "3") (pinfunction "D_3") (pintype "unspecified"))
    )
    (net (code "24") (name "Net-(D3-A)") (class "Default")
      (node (ref "D3") (pin "2") (pinfunction "A_2") (pintype "unspecified"))
      (node (ref "L1") (pin "1") (pinfunction "1_1") (pintype "unspecified"))
      (node (ref "U17") (pin "1") (pinfunction "SW_1") (pintype "unspecified"))
    )
    (net (code "25") (name "Net-(H3-Pad2)") (class "Default")
      (node (ref "H3") (pin "2") (pinfunction "2_2") (pintype "unspecified"))
      (node (ref "R18") (pin "2") (pinfunction "2_2") (pintype "unspecified"))
    )
    (net (code "26") (name "Net-(LED5-A)") (class "Default")
      (node (ref "LED5") (pin "1") (pinfunction "A_1") (pintype "unspecified"))
      (node (ref "R20") (pin "2") (pinfunction "2_2") (pintype "input"))
    )
    (net (code "27") (name "Net-(Q1-G)") (class "Default")
      (node (ref "Q1") (pin "1") (pinfunction "G_1") (pintype "unspecified"))
      (node (ref "R21") (pin "2") (pinfunction "2_2") (pintype "input"))
    )
    (net (code "28") (name "Net-(R2-Pad1)") (class "Default")
      (node (ref "R2") (pin "1") (pinfunction "1_1") (pintype "unspecified"))
      (node (ref "U10") (pin "1") (pinfunction "1_1") (pintype "unspecified"))
    )
    (net (code "29") (name "Net-(R2-Pad2)") (class "Default")
      (node (ref "R2") (pin "2") (pinfunction "2_2") (pintype "unspecified"))
      (node (ref "R3") (pin "1") (pinfunction "1_1") (pintype "unspecified"))
      (node (ref "R6") (pin "2") (pinfunction "2_2") (pintype "unspecified"))
    )
    (net (code "30") (name "Net-(U9-+IN)") (class "Default")
      (node (ref "D1") (pin "3") (pinfunction "3_3") (pintype "unspecified"))
      (node (ref "R6") (pin "1") (pinfunction "1_1") (pintype "unspecified"))
      (node (ref "U9") (pin "1") (pinfunction "+IN_1") (pintype "unspecified"))
    )
    (net (code "31") (name "Net-(U17-FB)") (class "Default")
      (node (ref "R22") (pin "1") (pinfunction "1_1") (pintype "input"))
      (node (ref "R23") (pin "2") (pinfunction "2_2") (pintype "input"))
      (node (ref "U17") (pin "3") (pinfunction "FB_3") (pintype "unspecified"))
    )
    (net (code "32") (name "Net-(U18-PB13)") (class "Default")
      (node (ref "R20") (pin "1") (pinfunction "1_1") (pintype "input"))
      (node (ref "U18") (pin "25") (pinfunction "PB13_25") (pintype "unspecified"))
    )
    (net (code "33") (name "unconnected-(SW3-Pad2)") (class "Default")
      (node (ref "SW3") (pin "2") (pinfunction "2_2") (pintype "unspecified"))
    )
    (net (code "34") (name "unconnected-(U9-N{slash}C-Pad2)") (class "Default")
      (node (ref "U9") (pin "2") (pinfunction "N/C_2") (pintype "unspecified"))
    )
    (net (code "35") (name "unconnected-(U9-N{slash}C-Pad5)") (class "Default")
      (node (ref "U9") (pin "5") (pinfunction "N/C_5") (pintype "unspecified"))
    )
    (net (code "36") (name "unconnected-(U9-N{slash}C-Pad7)") (class "Default")
      (node (ref "U9") (pin "7") (pinfunction "N/C_7") (pintype "unspecified"))
    )
    (net (code "37") (name "unconnected-(U11-INT2-Pad9)") (class "Default")
      (node (ref "U11") (pin "9") (pinfunction "INT2_9") (pintype "input"))
    )
    (net (code "38") (name "unconnected-(U11-NC-Pad10)") (class "Default")
      (node (ref "U11") (pin "10") (pinfunction "NC_10") (pintype "input"))
    )
    (net (code "39") (name "unconnected-(U11-NC-Pad11)") (class "Default")
      (node (ref "U11") (pin "11") (pinfunction "NC_11") (pintype "input"))
    )
    (net (code "40") (name "unconnected-(U11-SCx-Pad3)") (class "Default")
      (node (ref "U11") (pin "3") (pinfunction "SCx_3") (pintype "input"))
    )
    (net (code "41") (name "unconnected-(U11-SDO{slash}SA0-Pad1)") (class "Default")
      (node (ref "U11") (pin "1") (pinfunction "SDO/SA0_1") (pintype "input"))
    )
    (net (code "42") (name "unconnected-(U11-SDx-Pad2)") (class "Default")
      (node (ref "U11") (pin "2") (pinfunction "SDx_2") (pintype "input"))
    )
    (net (code "43") (name "unconnected-(U14-SDO-Pad6)") (class "Default")
      (node (ref "U14") (pin "6") (pinfunction "SDO_6") (pintype "unspecified"))
    )
    (net (code "44") (name "unconnected-(U17-NC-Pad6)") (class "Default")
      (node (ref "U17") (pin "6") (pinfunction "NC_6") (pintype "unspecified"))
    )
    (net (code "45") (name "unconnected-(U18-PA2-Pad13)") (class "Default")
      (node (ref "U18") (pin "13") (pinfunction "PA2_13") (pintype "unspecified"))
    )
    (net (code "46") (name "unconnected-(U18-PA5-Pad16)") (class "Default")
      (node (ref "U18") (pin "16") (pinfunction "PA5_16") (pintype "unspecified"))
    )
    (net (code "47") (name "unconnected-(U18-PA6-Pad17)") (class "Default")
      (node (ref "U18") (pin "17") (pinfunction "PA6_17") (pintype "unspecified"))
    )
    (net (code "48") (name "unconnected-(U18-PA7-Pad18)") (class "Default")
      (node (ref "U18") (pin "18") (pinfunction "PA7_18") (pintype "unspecified"))
    )
    (net (code "49") (name "unconnected-(U18-PA9-Pad29)") (class "Default")
      (node (ref "U18") (pin "29") (pinfunction "PA9_29") (pintype "unspecified"))
    )
    (net (code "50") (name "unconnected-(U18-PA10-Pad32)") (class "Default")
      (node (ref "U18") (pin "32") (pinfunction "PA10_32") (pintype "unspecified"))
    )
    (net (code "51") (name "unconnected-(U18-PA11[PA9]-Pad33)") (class "Default")
      (node (ref "U18") (pin "33") (pinfunction "PA11[PA9]_33") (pintype "unspecified"))
    )
    (net (code "52") (name "unconnected-(U18-PA12[PA10]-Pad34)") (class "Default")
      (node (ref "U18") (pin "34") (pinfunction "PA12[PA10]_34") (pintype "unspecified"))
    )
    (net (code "53") (name "unconnected-(U18-PA15-Pad37)") (class "Default")
      (node (ref "U18") (pin "37") (pinfunction "PA15_37") (pintype "unspecified"))
    )
    (net (code "54") (name "unconnected-(U18-PB2-Pad21)") (class "Default")
      (node (ref "U18") (pin "21") (pinfunction "PB2_21") (pintype "unspecified"))
    )
    (net (code "55") (name "unconnected-(U18-PB3-Pad42)") (class "Default")
      (node (ref "U18") (pin "42") (pinfunction "PB3_42") (pintype "unspecified"))
    )
    (net (code "56") (name "unconnected-(U18-PB4-Pad43)") (class "Default")
      (node (ref "U18") (pin "43") (pinfunction "PB4_43") (pintype "unspecified"))
    )
    (net (code "57") (name "unconnected-(U18-PB5-Pad44)") (class "Default")
      (node (ref "U18") (pin "44") (pinfunction "PB5_44") (pintype "unspecified"))
    )
    (net (code "58") (name "unconnected-(U18-PB8-Pad47)") (class "Default")
      (node (ref "U18") (pin "47") (pinfunction "PB8_47") (pintype "unspecified"))
    )
    (net (code "59") (name "unconnected-(U18-PB9-Pad48)") (class "Default")
      (node (ref "U18") (pin "48") (pinfunction "PB9_48") (pintype "unspecified"))
    )
    (net (code "60") (name "unconnected-(U18-PB10-Pad22)") (class "Default")
      (node (ref "U18") (pin "22") (pinfunction "PB10_22") (pintype "unspecified"))
    )
    (net (code "61") (name "unconnected-(U18-PB11-Pad23)") (class "Default")
      (node (ref "U18") (pin "23") (pinfunction "PB11_23") (pintype "unspecified"))
    )
    (net (code "62") (name "unconnected-(U18-PB12-Pad24)") (class "Default")
      (node (ref "U18") (pin "24") (pinfunction "PB12_24") (pintype "unspecified"))
    )
    (net (code "63") (name "unconnected-(U18-PB14-Pad26)") (class "Default")
      (node (ref "U18") (pin "26") (pinfunction "PB14_26") (pintype "unspecified"))
    )
    (net (code "64") (name "unconnected-(U18-PB15-Pad27)") (class "Default")
      (node (ref "U18") (pin "27") (pinfunction "PB15_27") (pintype "unspecified"))
    )
    (net (code "65") (name "unconnected-(U18-PC6-Pad30)") (class "Default")
      (node (ref "U18") (pin "30") (pinfunction "PC6_30") (pintype "unspecified"))
    )
    (net (code "66") (name "unconnected-(U18-PC13-Pad1)") (class "Default")
      (node (ref "U18") (pin "1") (pinfunction "PC13_1") (pintype "unspecified"))
    )
    (net (code "67") (name "unconnected-(U18-PC14-OSC32_IN-Pad2)") (class "Default")
      (node (ref "U18") (pin "2") (pinfunction "PC14-OSC32_IN_2") (pintype "unspecified"))
    )
    (net (code "68") (name "unconnected-(U18-PC15-OSC32_OUT-Pad3)") (class "Default")
      (node (ref "U18") (pin "3") (pinfunction "PC15-OSC32_OUT_3") (pintype "unspecified"))
    )
    (net (code "69") (name "unconnected-(U18-PD0-Pad38)") (class "Default")
      (node (ref "U18") (pin "38") (pinfunction "PD0_38") (pintype "unspecified"))
    )
    (net (code "70") (name "unconnected-(U18-PD1-Pad39)") (class "Default")
      (node (ref "U18") (pin "39") (pinfunction "PD1_39") (pintype "unspecified"))
    )
    (net (code "71") (name "unconnected-(U18-PD2-Pad40)") (class "Default")
      (node (ref "U18") (pin "40") (pinfunction "PD2_40") (pintype "unspecified"))
    )
    (net (code "72") (name "unconnected-(U18-PD3-Pad41)") (class "Default")
      (node (ref "U18") (pin "41") (pinfunction "PD3_41") (pintype "unspecified"))
    )
    (net (code "73") (name "unconnected-(U18-PF2-NRST-Pad10)") (class "Default")
      (node (ref "U18") (pin "10") (pinfunction "PF2-NRST_10") (pintype "unspecified"))
    )
  )
)
